# Wireless_Controller_V1_1.net
KiCad netlist of a schematic drawn in Altium Designer
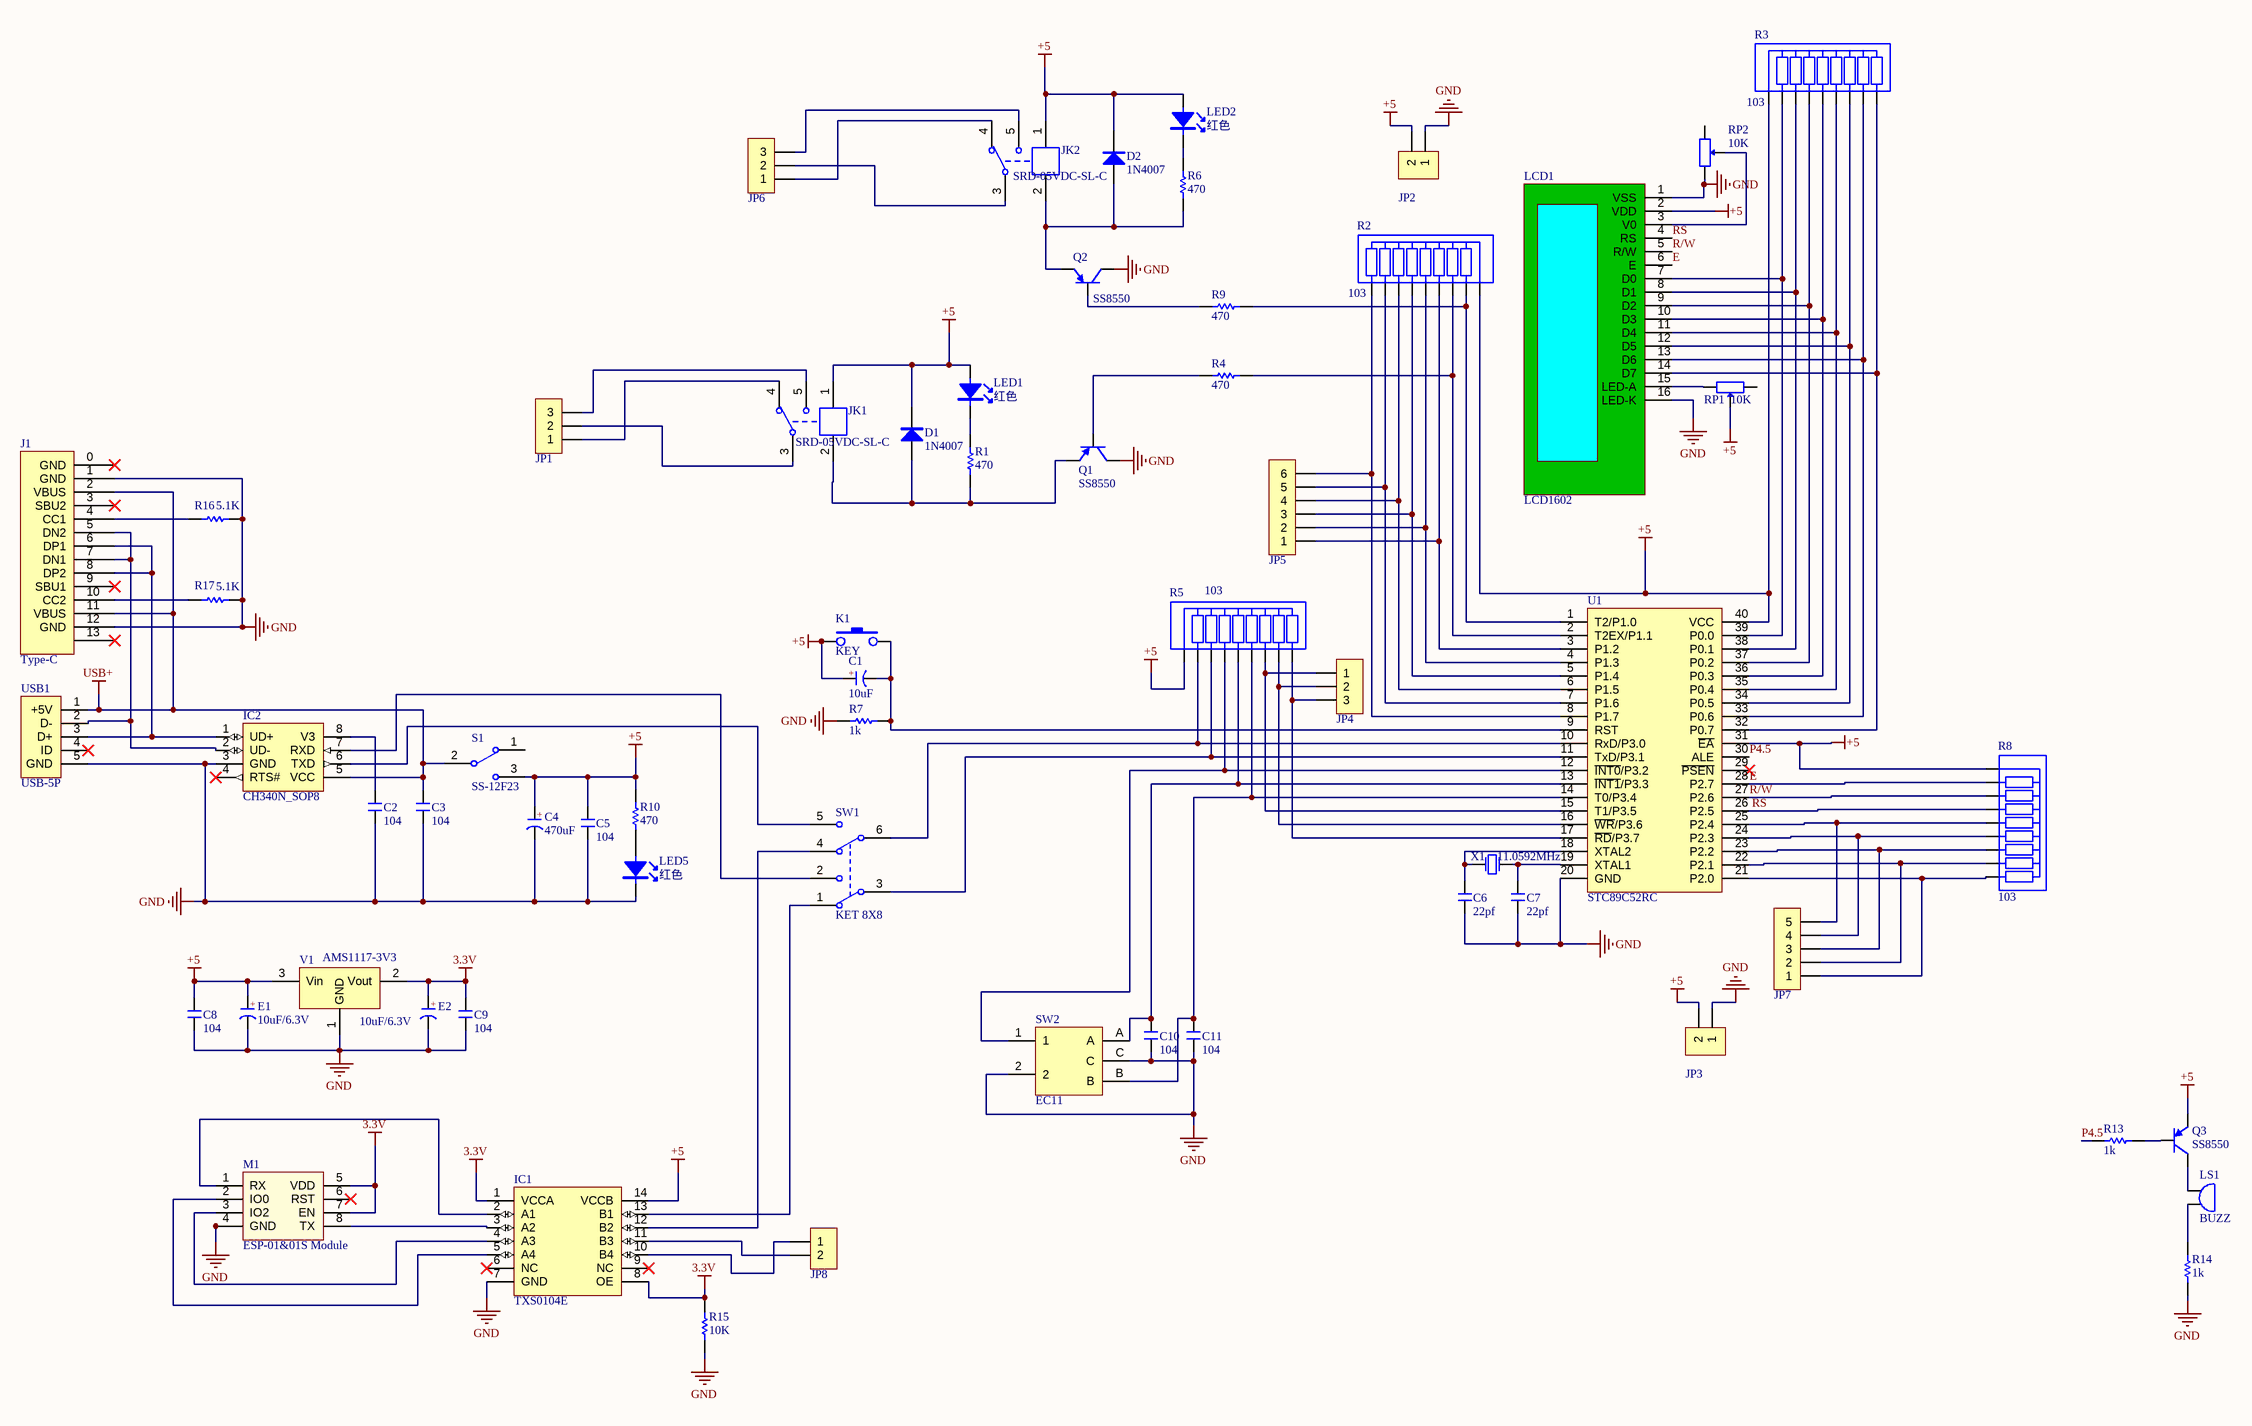
[diagram p0: Wireless_Controller_V1.1.SchDoc]

(export (version "E")
  (design (tool "Eeschema 10.0.6"))
  (components
    (comp (ref "C1")
      (value "10uF")
      (footprint "CAP 1.5*4*8")
      (description "直插电解电容")
      (libsource (lib "") (part "CE_1"))
    )
    (comp (ref "C2")
      (value "104")
      (footprint "CC 1.8*3.6")
      (description "瓷片电容")
      (libsource (lib "01 - 电容-电阻-电感") (part "CC"))
    )
    (comp (ref "C3")
      (value "104")
      (footprint "CC 1.8*3.6")
      (description "瓷片电容")
      (libsource (lib "01 - 电容-电阻-电感") (part "CC"))
    )
    (comp (ref "C4")
      (value "470uF")
      (footprint "CAP 2.5*6.3*11.2 - BK")
      (description "直插电解电容")
      (libsource (lib "01 - 电容-电阻-电感") (part "CE"))
    )
    (comp (ref "C5")
      (value "104")
      (footprint "CC 1.8*3.6")
      (description "瓷片电容")
      (libsource (lib "01 - 电容-电阻-电感") (part "CC"))
    )
    (comp (ref "C6")
      (value "22pf")
      (footprint "CC 1.8*3.6")
      (description "瓷片电容")
      (libsource (lib "01 - 电容-电阻-电感") (part "CC"))
    )
    (comp (ref "C7")
      (value "22pf")
      (footprint "CC 1.8*3.6")
      (description "瓷片电容")
      (libsource (lib "01 - 电容-电阻-电感") (part "CC"))
    )
    (comp (ref "C8")
      (value "104")
      (footprint "CC 1.8*3.6")
      (description "瓷片电容")
      (libsource (lib "01 - 电容-电阻-电感") (part "CC"))
    )
    (comp (ref "C9")
      (value "104")
      (footprint "CC 1.8*3.6")
      (description "瓷片电容")
      (libsource (lib "01 - 电容-电阻-电感") (part "CC"))
    )
    (comp (ref "C10")
      (value "104")
      (footprint "CC 1.8*3.6")
      (description "瓷片电容")
      (libsource (lib "01 - 电容-电阻-电感") (part "CC"))
    )
    (comp (ref "C11")
      (value "104")
      (footprint "CC 1.8*3.6")
      (description "瓷片电容")
      (libsource (lib "01 - 电容-电阻-电感") (part "CC"))
    )
    (comp (ref "D1")
      (value "1N4007")
      (footprint "DO-41")
      (description "整流二极管")
      (libsource (lib "02 - 二极管(LED)-三极管-整流桥") (part "1N4007"))
    )
    (comp (ref "D2")
      (value "1N4007")
      (footprint "DO-41")
      (description "整流二极管")
      (libsource (lib "02 - 二极管(LED)-三极管-整流桥") (part "1N4007"))
    )
    (comp (ref "E1")
      (value "10uF/6.3V")
      (footprint "CD S(2012)")
      (description "贴片钽电容")
      (libsource (lib "01 - 电容-电阻-电感") (part "CT"))
    )
    (comp (ref "E2")
      (value "10uF/6.3V")
      (footprint "CD S(2012)")
      (description "贴片钽电容")
      (libsource (lib "01 - 电容-电阻-电感") (part "CT"))
    )
    (comp (ref "IC1")
      (value "TXS0104E")
      (footprint "13 - TSSOP封装:TSSOP14_L")
      (description "TXS0104E_TSSOP(14pin)")
      (libsource (lib "TXS0104E_TSSOP(14pin)") (part "TXS0104E"))
    )
    (comp (ref "IC2")
      (value "CH340N_SOP8")
      (footprint "10 - SOP-SOIC封装:SOP8")
      (description "USB转串口芯片")
      (libsource (lib "CH340N_SOP-8") (part "CH340N_SOP8"))
    )
    (comp (ref "J1")
      (value "Type-C")
      (footprint "Type-C_16pin")
      (libsource (lib "Type-C_16PIN") (part "Type-C_16pin"))
    )
    (comp (ref "JK1")
      (value "SRD-05VDC-SL-C")
      (footprint "SRD-C_B")
      (description "继电器  5V一组转换")
      (libsource (lib "07 - 继电器-变压器-各种模块") (part "SRD-05VDC-SL-C"))
    )
    (comp (ref "JK2")
      (value "SRD-05VDC-SL-C")
      (footprint "SRD-C_B")
      (description "继电器  5V一组转换")
      (libsource (lib "07 - 继电器-变压器-各种模块") (part "SRD-05VDC-SL-C"))
    )
    (comp (ref "JP1")
      (value "HDR-1X3")
      (footprint "KF7620-3P")
      (description "3P接插件")
      (libsource (lib "24 - 接插件-脚距7.62mm (300mil) ") (part "Header 3"))
    )
    (comp (ref "JP2")
      (value "HDR-1X2")
      (footprint "KF7620-2P")
      (description "2P接插件")
      (libsource (lib "24 - 接插件-脚距7.62mm (300mil) ") (part "Header 2"))
    )
    (comp (ref "JP3")
      (value "HDR-1X2")
      (footprint "KF7620-2P")
      (description "2P接插件")
      (libsource (lib "24 - 接插件-脚距7.62mm (300mil) ") (part "Header 2"))
    )
    (comp (ref "JP4")
      (value "HDR-1X3")
      (footprint "KF301-5.0-3P")
      (description "3P接插件")
      (libsource (lib "22 - 接插件-脚距5.0mm") (part "Header 3"))
    )
    (comp (ref "JP5")
      (value "HDR-1X6")
      (footprint "KF301-5.0-6P")
      (description "6P接插件")
      (libsource (lib "22 - 接插件-脚距5.0mm") (part "Header 6"))
    )
    (comp (ref "JP6")
      (value "HDR-1X3")
      (footprint "KF7620-3P")
      (description "3P接插件")
      (libsource (lib "24 - 接插件-脚距7.62mm (300mil) ") (part "Header 3"))
    )
    (comp (ref "JP7")
      (value "HDR-1X5")
      (footprint "KF301-5.0-5P")
      (description "5P接插件")
      (libsource (lib "22 - 接插件-脚距5.0mm") (part "Header 5"))
    )
    (comp (ref "JP8")
      (value "HDR-1X2")
      (footprint "KF301-5.0-2P")
      (description "2P接插件")
      (libsource (lib "22 - 接插件-脚距5.0mm") (part "Header 2"))
    )
    (comp (ref "K1")
      (value "KEY")
      (footprint "TSW DIP-6*6*5")
      (description "四角直插开关")
      (libsource (lib "03 - 按键-开关-晶振-蜂鸣器") (part "KEY"))
    )
    (comp (ref "LCD1")
      (value "LCD1602")
      (footprint "LCD-1602")
      (libsource (lib "05 - 点阵-液晶-数码管-TFT") (part "LCD1602"))
    )
    (comp (ref "LED1")
      (value "红色")
      (footprint "LED 3MM-R")
      (description "插件LED")
      (libsource (lib "02 - 二极管(LED)-三极管-整流桥") (part "LED-3MM"))
    )
    (comp (ref "LED2")
      (value "红色")
      (footprint "LED 3MM-R")
      (description "插件LED")
      (libsource (lib "02 - 二极管(LED)-三极管-整流桥") (part "LED-3MM"))
    )
    (comp (ref "LED5")
      (value "红色")
      (footprint "LED 3MM-R")
      (description "插件LED")
      (libsource (lib "02 - 二极管(LED)-三极管-整流桥") (part "LED-3MM"))
    )
    (comp (ref "LS1")
      (value "BUZZ")
      (footprint "BEEP 6.5x12x8.5")
      (description "蜂鸣器")
      (libsource (lib "03 - 按键-开关-晶振-蜂鸣器") (part "BUZZ"))
    )
    (comp (ref "M1")
      (value "ESP-01&01S Module")
      (footprint "ESP-01&01S Module")
      (libsource (lib "ESP-01&01S Module") (part "ESP-01&01S Module"))
    )
    (comp (ref "Q1")
      (value "SS8550")
      (footprint "TO92A")
      (description "高频放大-PNP型")
      (libsource (lib "02 - 二极管(LED)-三极管-整流桥") (part "8550-DIP"))
    )
    (comp (ref "Q2")
      (value "SS8550")
      (footprint "TO92A")
      (description "高频放大-PNP型")
      (libsource (lib "02 - 二极管(LED)-三极管-整流桥") (part "8550-DIP"))
    )
    (comp (ref "Q3")
      (value "SS8550")
      (footprint "TO92A")
      (description "高频放大-PNP型")
      (libsource (lib "02 - 二极管(LED)-三极管-整流桥") (part "8550-DIP"))
    )
    (comp (ref "R1")
      (value "470")
      (footprint "RS 1/4W")
      (description "色环电阻")
      (libsource (lib "01 - 电容-电阻-电感") (part "Res"))
    )
    (comp (ref "R2")
      (value "103")
      (footprint "R SIP9-2.54")
      (description "9脚直插排阻")
      (libsource (lib "01 - 电容-电阻-电感") (part "R SIP9"))
    )
    (comp (ref "R3")
      (value "103")
      (footprint "R SIP9-2.54")
      (description "9脚直插排阻")
      (libsource (lib "01 - 电容-电阻-电感") (part "R SIP9"))
    )
    (comp (ref "R4")
      (value "470")
      (footprint "RS 1/4W")
      (description "色环电阻")
      (libsource (lib "01 - 电容-电阻-电感") (part "Res"))
    )
    (comp (ref "R5")
      (value "103")
      (footprint "R SIP9-2.54")
      (description "9脚直插排阻")
      (libsource (lib "01 - 电容-电阻-电感") (part "R SIP9"))
    )
    (comp (ref "R6")
      (value "470")
      (footprint "RS 1/4W")
      (description "色环电阻")
      (libsource (lib "01 - 电容-电阻-电感") (part "Res"))
    )
    (comp (ref "R7")
      (value "1k")
      (footprint "RS 1/4W")
      (description "色环电阻")
      (libsource (lib "01 - 电容-电阻-电感") (part "Res"))
    )
    (comp (ref "R8")
      (value "103")
      (footprint "R SIP9-2.54")
      (description "9脚直插排阻")
      (libsource (lib "01 - 电容-电阻-电感") (part "R SIP9"))
    )
    (comp (ref "R9")
      (value "470")
      (footprint "RS 1/4W")
      (description "色环电阻")
      (libsource (lib "01 - 电容-电阻-电感") (part "Res"))
    )
    (comp (ref "R10")
      (value "470")
      (footprint "RS 1/4W")
      (description "色环电阻")
      (libsource (lib "01 - 电容-电阻-电感") (part "Res"))
    )
    (comp (ref "R13")
      (value "1k")
      (footprint "RS 1/4W")
      (description "色环电阻")
      (libsource (lib "01 - 电容-电阻-电感") (part "Res"))
    )
    (comp (ref "R14")
      (value "1k")
      (footprint "RS 1/4W")
      (description "色环电阻")
      (libsource (lib "01 - 电容-电阻-电感") (part "Res"))
    )
    (comp (ref "R15")
      (value "10K")
      (footprint "RS 1/4W")
      (description "色环电阻")
      (libsource (lib "01 - 电容-电阻-电感") (part "Res"))
    )
    (comp (ref "R16")
      (value "5.1K")
      (footprint "RS 1/4W")
      (description "色环电阻")
      (libsource (lib "01 - 电容-电阻-电感") (part "Res"))
    )
    (comp (ref "R17")
      (value "5.1K")
      (footprint "RS 1/4W")
      (description "色环电阻")
      (libsource (lib "01 - 电容-电阻-电感") (part "Res"))
    )
    (comp (ref "RP1")
      (value "10K")
      (footprint "3296W")
      (description "单联电位器")
      (libsource (lib "01 - 电容-电阻-电感") (part "RP"))
    )
    (comp (ref "RP2")
      (value "10K")
      (footprint "3296W")
      (description "单联电位器")
      (libsource (lib "01 - 电容-电阻-电感") (part "RP"))
    )
    (comp (ref "S1")
      (value "SS-12F23")
      (footprint "SS-12D10")
      (description "1路波动开关")
      (libsource (lib "03 - 按键-开关-晶振-蜂鸣器") (part "SSW-1P"))
    )
    (comp (ref "SW1")
      (value "KET 8X8")
      (footprint "KFT DIP-8X8")
      (description "8*8自锁开关")
      (libsource (lib "03 - 按键-开关-晶振-蜂鸣器") (part "KET 8X8"))
    )
    (comp (ref "SW2")
      (value "EC11")
      (footprint "EC11")
      (description "数字开关编码器")
      (libsource (lib "03 - 按键-开关-晶振-蜂鸣器") (part "SW-EC11"))
    )
    (comp (ref "U1")
      (value "STC89C52RC")
      (footprint "DIP40-600")
      (description "STC单片机")
      (libsource (lib "26 - STC系列单片机") (part "STC89C52RC"))
    )
    (comp (ref "USB1")
      (value "USB-5P")
      (footprint "USB-MICRO_A")
      (description "微型USB母座")
      (libsource (lib "04 - 接口类-USB接口-网口") (part "USB-5P"))
    )
    (comp (ref "V1")
      (value "AMS1117-3V3")
      (footprint "SOT223_L")
      (description "三端稳压芯片")
      (libsource (lib "08 - 稳压芯片-电源管理芯片") (part "AMS1117"))
    )
    (comp (ref "X1")
      (value "11.0592MHz")
      (footprint "OSC HC-49S")
      (description "2脚无源脚晶振")
      (libsource (lib "03 - 按键-开关-晶振-蜂鸣器") (part "XTAL-2P"))
    )
  )
  (nets
    (net (code "1") (name "+5") (class "Default")
      (node (ref "C1") (pin "1") (pinfunction "A_1") (pintype "passive"))
      (node (ref "C4") (pin "1") (pinfunction "A_1") (pintype "passive"))
      (node (ref "C5") (pin "2") (pinfunction "2_2") (pintype "passive"))
      (node (ref "C8") (pin "2") (pinfunction "2_2") (pintype "passive"))
      (node (ref "D1") (pin "2") (pinfunction "K_2") (pintype "passive"))
      (node (ref "D2") (pin "2") (pinfunction "K_2") (pintype "passive"))
      (node (ref "E1") (pin "1") (pinfunction "A_1") (pintype "passive"))
      (node (ref "IC1") (pin "14") (pinfunction "VCCB_14") (pintype "power_in"))
      (node (ref "JK1") (pin "1") (pinfunction "1_1") (pintype "passive"))
      (node (ref "JK2") (pin "1") (pinfunction "1_1") (pintype "passive"))
      (node (ref "JP2") (pin "2") (pinfunction "2_2") (pintype "passive"))
      (node (ref "JP3") (pin "2") (pinfunction "2_2") (pintype "passive"))
      (node (ref "K1") (pin "1") (pinfunction "1_1") (pintype "passive"))
      (node (ref "LCD1") (pin "2") (pinfunction "VDD_2") (pintype "passive"))
      (node (ref "LED1") (pin "1") (pinfunction "A_1") (pintype "passive"))
      (node (ref "LED2") (pin "1") (pinfunction "A_1") (pintype "passive"))
      (node (ref "Q3") (pin "1") (pinfunction "E_1") (pintype "passive"))
      (node (ref "R10") (pin "2") (pinfunction "2_2") (pintype "passive"))
      (node (ref "R2") (pin "1") (pinfunction "1_1") (pintype "passive"))
      (node (ref "R3") (pin "1") (pinfunction "1_1") (pintype "passive"))
      (node (ref "R5") (pin "1") (pinfunction "1_1") (pintype "passive"))
      (node (ref "R8") (pin "1") (pinfunction "1_1") (pintype "passive"))
      (node (ref "RP1") (pin "2") (pinfunction "2_2") (pintype "passive"))
      (node (ref "S1") (pin "3") (pinfunction "3_3") (pintype "passive"))
      (node (ref "U1") (pin "31") (pinfunction "~{EA}_31") (pintype "passive"))
      (node (ref "U1") (pin "40") (pinfunction "VCC_40") (pintype "passive"))
      (node (ref "V1") (pin "3") (pinfunction "Vin_3") (pintype "passive"))
    )
    (net (code "2") (name "/E") (class "Default")
      (node (ref "LCD1") (pin "6") (pinfunction "E_6") (pintype "passive"))
      (node (ref "R8") (pin "2") (pinfunction "2_2") (pintype "passive"))
      (node (ref "U1") (pin "28") (pinfunction "P2.7_28") (pintype "passive"))
    )
    (net (code "3") (name "/P4.5") (class "Default")
      (node (ref "R13") (pin "2") (pinfunction "2_2") (pintype "passive"))
      (node (ref "U1") (pin "30") (pinfunction "ALE_30") (pintype "passive"))
    )
    (net (code "4") (name "/RS") (class "Default")
      (node (ref "LCD1") (pin "4") (pinfunction "RS_4") (pintype "passive"))
      (node (ref "R8") (pin "4") (pinfunction "4_4") (pintype "passive"))
      (node (ref "U1") (pin "26") (pinfunction "P2.5_26") (pintype "passive"))
    )
    (net (code "5") (name "/R{slash}W") (class "Default")
      (node (ref "LCD1") (pin "5") (pinfunction "R/W_5") (pintype "passive"))
      (node (ref "R8") (pin "3") (pinfunction "3_3") (pintype "passive"))
      (node (ref "U1") (pin "27") (pinfunction "P2.6_27") (pintype "passive"))
    )
    (net (code "6") (name "3.3V") (class "Default")
      (node (ref "C9") (pin "2") (pinfunction "2_2") (pintype "passive"))
      (node (ref "E2") (pin "1") (pinfunction "A_1") (pintype "passive"))
      (node (ref "IC1") (pin "1") (pinfunction "VCCA_1") (pintype "power_in"))
      (node (ref "IC1") (pin "8") (pinfunction "OE_8") (pintype "passive"))
      (node (ref "M1") (pin "5") (pinfunction "VDD_5") (pintype "passive"))
      (node (ref "M1") (pin "7") (pinfunction "EN_7") (pintype "passive"))
      (node (ref "R15") (pin "2") (pinfunction "2_2") (pintype "passive"))
      (node (ref "V1") (pin "2") (pinfunction "Vout_2") (pintype "passive"))
    )
    (net (code "7") (name "GND") (class "Default")
      (node (ref "C10") (pin "1") (pinfunction "1_1") (pintype "passive"))
      (node (ref "C11") (pin "1") (pinfunction "1_1") (pintype "passive"))
      (node (ref "C2") (pin "1") (pinfunction "1_1") (pintype "passive"))
      (node (ref "C3") (pin "1") (pinfunction "1_1") (pintype "passive"))
      (node (ref "C4") (pin "2") (pinfunction "K_2") (pintype "passive"))
      (node (ref "C5") (pin "1") (pinfunction "1_1") (pintype "passive"))
      (node (ref "C6") (pin "1") (pinfunction "1_1") (pintype "passive"))
      (node (ref "C7") (pin "1") (pinfunction "1_1") (pintype "passive"))
      (node (ref "C8") (pin "1") (pinfunction "1_1") (pintype "passive"))
      (node (ref "C9") (pin "1") (pinfunction "1_1") (pintype "passive"))
      (node (ref "E1") (pin "2") (pinfunction "K_2") (pintype "passive"))
      (node (ref "E2") (pin "2") (pinfunction "K_2") (pintype "passive"))
      (node (ref "IC1") (pin "7") (pinfunction "GND_7") (pintype "power_in"))
      (node (ref "IC2") (pin "3") (pinfunction "GND_3") (pintype "power_in"))
      (node (ref "J1") (pin "1") (pinfunction "GND_1") (pintype "passive"))
      (node (ref "J1") (pin "12") (pinfunction "GND_12") (pintype "passive"))
      (node (ref "JP2") (pin "1") (pinfunction "1_1") (pintype "passive"))
      (node (ref "JP3") (pin "1") (pinfunction "1_1") (pintype "passive"))
      (node (ref "LCD1") (pin "1") (pinfunction "VSS_1") (pintype "passive"))
      (node (ref "LCD1") (pin "16") (pinfunction "LED-K_16") (pintype "passive"))
      (node (ref "LED5") (pin "2") (pinfunction "K_2") (pintype "passive"))
      (node (ref "M1") (pin "4") (pinfunction "GND_4") (pintype "passive"))
      (node (ref "Q1") (pin "3") (pinfunction "C_3") (pintype "passive"))
      (node (ref "Q2") (pin "3") (pinfunction "C_3") (pintype "passive"))
      (node (ref "R14") (pin "2") (pinfunction "2_2") (pintype "passive"))
      (node (ref "R15") (pin "1") (pinfunction "1_1") (pintype "passive"))
      (node (ref "R16") (pin "2") (pinfunction "2_2") (pintype "passive"))
      (node (ref "R17") (pin "2") (pinfunction "2_2") (pintype "passive"))
      (node (ref "R7") (pin "2") (pinfunction "2_2") (pintype "passive"))
      (node (ref "RP2") (pin "3") (pinfunction "3_3") (pintype "passive"))
      (node (ref "SW2") (pin "2") (pinfunction "2_2") (pintype "passive"))
      (node (ref "SW2") (pin "C") (pinfunction "C_C") (pintype "passive"))
      (node (ref "U1") (pin "20") (pinfunction "GND_20") (pintype "passive"))
      (node (ref "USB1") (pin "5") (pinfunction "GND_5") (pintype "passive"))
      (node (ref "V1") (pin "1") (pinfunction "GND_1") (pintype "passive"))
    )
    (net (code "8") (name "Net-(C1-K)") (class "Default")
      (node (ref "C1") (pin "2") (pinfunction "K_2") (pintype "passive"))
      (node (ref "K1") (pin "2") (pinfunction "2_2") (pintype "passive"))
      (node (ref "R7") (pin "1") (pinfunction "1_1") (pintype "passive"))
      (node (ref "U1") (pin "9") (pinfunction "RST_9") (pintype "passive"))
    )
    (net (code "9") (name "Net-(D1-A)") (class "Default")
      (node (ref "D1") (pin "1") (pinfunction "A_1") (pintype "passive"))
      (node (ref "JK1") (pin "2") (pinfunction "2_2") (pintype "passive"))
      (node (ref "Q1") (pin "1") (pinfunction "E_1") (pintype "passive"))
      (node (ref "R1") (pin "2") (pinfunction "2_2") (pintype "passive"))
    )
    (net (code "10") (name "Net-(D2-A)") (class "Default")
      (node (ref "D2") (pin "1") (pinfunction "A_1") (pintype "passive"))
      (node (ref "JK2") (pin "2") (pinfunction "2_2") (pintype "passive"))
      (node (ref "Q2") (pin "1") (pinfunction "E_1") (pintype "passive"))
      (node (ref "R6") (pin "2") (pinfunction "2_2") (pintype "passive"))
    )
    (net (code "11") (name "Net-(IC1-A1)") (class "Default")
      (node (ref "IC1") (pin "2") (pinfunction "A1_2") (pintype "bidirectional"))
      (node (ref "M1") (pin "1") (pinfunction "RX_1") (pintype "passive"))
    )
    (net (code "12") (name "Net-(IC1-A2)") (class "Default")
      (node (ref "IC1") (pin "3") (pinfunction "A2_3") (pintype "bidirectional"))
      (node (ref "M1") (pin "8") (pinfunction "TX_8") (pintype "passive"))
    )
    (net (code "13") (name "Net-(IC1-A3)") (class "Default")
      (node (ref "IC1") (pin "4") (pinfunction "A3_4") (pintype "bidirectional"))
      (node (ref "M1") (pin "3") (pinfunction "IO2_3") (pintype "passive"))
    )
    (net (code "14") (name "Net-(IC1-A4)") (class "Default")
      (node (ref "IC1") (pin "5") (pinfunction "A4_5") (pintype "bidirectional"))
      (node (ref "M1") (pin "2") (pinfunction "IO0_2") (pintype "passive"))
    )
    (net (code "15") (name "Net-(IC1-B1)") (class "Default")
      (node (ref "IC1") (pin "13") (pinfunction "B1_13") (pintype "bidirectional"))
      (node (ref "SW1") (pin "1") (pinfunction "NC1_1") (pintype "passive"))
    )
    (net (code "16") (name "Net-(IC1-B2)") (class "Default")
      (node (ref "IC1") (pin "12") (pinfunction "B2_12") (pintype "bidirectional"))
      (node (ref "SW1") (pin "4") (pinfunction "NO2_4") (pintype "passive"))
    )
    (net (code "17") (name "Net-(IC1-B3)") (class "Default")
      (node (ref "IC1") (pin "11") (pinfunction "B3_11") (pintype "bidirectional"))
      (node (ref "JP8") (pin "2") (pinfunction "2_2") (pintype "passive"))
    )
    (net (code "18") (name "Net-(IC1-B4)") (class "Default")
      (node (ref "IC1") (pin "10") (pinfunction "B4_10") (pintype "bidirectional"))
      (node (ref "JP8") (pin "1") (pinfunction "1_1") (pintype "passive"))
    )
    (net (code "19") (name "Net-(IC2-RXD)") (class "Default")
      (node (ref "IC2") (pin "7") (pinfunction "RXD_7") (pintype "input"))
      (node (ref "SW1") (pin "2") (pinfunction "COM2_2") (pintype "passive"))
    )
    (net (code "20") (name "Net-(IC2-TXD)") (class "Default")
      (node (ref "IC2") (pin "6") (pinfunction "TXD_6") (pintype "output"))
      (node (ref "SW1") (pin "5") (pinfunction "COM2_5") (pintype "passive"))
    )
    (net (code "21") (name "Net-(IC2-UD+)") (class "Default")
      (node (ref "IC2") (pin "1") (pinfunction "UD+_1") (pintype "bidirectional"))
      (node (ref "J1") (pin "6") (pinfunction "DP1_6") (pintype "passive"))
      (node (ref "J1") (pin "8") (pinfunction "DP2_8") (pintype "passive"))
      (node (ref "USB1") (pin "3") (pinfunction "D+_3") (pintype "passive"))
    )
    (net (code "22") (name "Net-(IC2-UD-)") (class "Default")
      (node (ref "IC2") (pin "2") (pinfunction "UD-_2") (pintype "bidirectional"))
      (node (ref "J1") (pin "5") (pinfunction "DN2_5") (pintype "passive"))
      (node (ref "J1") (pin "7") (pinfunction "DN1_7") (pintype "passive"))
      (node (ref "USB1") (pin "2") (pinfunction "D-_2") (pintype "passive"))
    )
    (net (code "23") (name "Net-(IC2-V3)") (class "Default")
      (node (ref "C2") (pin "2") (pinfunction "2_2") (pintype "passive"))
      (node (ref "IC2") (pin "8") (pinfunction "V3_8") (pintype "passive"))
    )
    (net (code "24") (name "Net-(J1-CC1)") (class "Default")
      (node (ref "J1") (pin "4") (pinfunction "CC1_4") (pintype "passive"))
      (node (ref "R16") (pin "1") (pinfunction "1_1") (pintype "passive"))
    )
    (net (code "25") (name "Net-(J1-CC2)") (class "Default")
      (node (ref "J1") (pin "10") (pinfunction "CC2_10") (pintype "passive"))
      (node (ref "R17") (pin "1") (pinfunction "1_1") (pintype "passive"))
    )
    (net (code "26") (name "Net-(JK1-Pad3)") (class "Default")
      (node (ref "JK1") (pin "3") (pinfunction "3_3") (pintype "passive"))
      (node (ref "JP1") (pin "2") (pinfunction "2_2") (pintype "passive"))
    )
    (net (code "27") (name "Net-(JK1-Pad4)") (class "Default")
      (node (ref "JK1") (pin "4") (pinfunction "4_4") (pintype "passive"))
      (node (ref "JP1") (pin "1") (pinfunction "1_1") (pintype "passive"))
    )
    (net (code "28") (name "Net-(JK1-Pad5)") (class "Default")
      (node (ref "JK1") (pin "5") (pinfunction "5_5") (pintype "passive"))
      (node (ref "JP1") (pin "3") (pinfunction "3_3") (pintype "passive"))
    )
    (net (code "29") (name "Net-(JK2-Pad3)") (class "Default")
      (node (ref "JK2") (pin "3") (pinfunction "3_3") (pintype "passive"))
      (node (ref "JP6") (pin "2") (pinfunction "2_2") (pintype "passive"))
    )
    (net (code "30") (name "Net-(JK2-Pad4)") (class "Default")
      (node (ref "JK2") (pin "4") (pinfunction "4_4") (pintype "passive"))
      (node (ref "JP6") (pin "1") (pinfunction "1_1") (pintype "passive"))
    )
    (net (code "31") (name "Net-(JK2-Pad5)") (class "Default")
      (node (ref "JK2") (pin "5") (pinfunction "5_5") (pintype "passive"))
      (node (ref "JP6") (pin "3") (pinfunction "3_3") (pintype "passive"))
    )
    (net (code "32") (name "Net-(LCD1-D0)") (class "Default")
      (node (ref "LCD1") (pin "7") (pinfunction "D0_7") (pintype "passive"))
      (node (ref "R3") (pin "2") (pinfunction "2_2") (pintype "passive"))
      (node (ref "U1") (pin "39") (pinfunction "P0.0_39") (pintype "passive"))
    )
    (net (code "33") (name "Net-(LCD1-D1)") (class "Default")
      (node (ref "LCD1") (pin "8") (pinfunction "D1_8") (pintype "passive"))
      (node (ref "R3") (pin "3") (pinfunction "3_3") (pintype "passive"))
      (node (ref "U1") (pin "38") (pinfunction "P0.1_38") (pintype "passive"))
    )
    (net (code "34") (name "Net-(LCD1-D2)") (class "Default")
      (node (ref "LCD1") (pin "9") (pinfunction "D2_9") (pintype "passive"))
      (node (ref "R3") (pin "4") (pinfunction "4_4") (pintype "passive"))
      (node (ref "U1") (pin "37") (pinfunction "P0.2_37") (pintype "passive"))
    )
    (net (code "35") (name "Net-(LCD1-D3)") (class "Default")
      (node (ref "LCD1") (pin "10") (pinfunction "D3_10") (pintype "passive"))
      (node (ref "R3") (pin "5") (pinfunction "5_5") (pintype "passive"))
      (node (ref "U1") (pin "36") (pinfunction "P0.3_36") (pintype "passive"))
    )
    (net (code "36") (name "Net-(LCD1-D4)") (class "Default")
      (node (ref "LCD1") (pin "11") (pinfunction "D4_11") (pintype "passive"))
      (node (ref "R3") (pin "6") (pinfunction "6_6") (pintype "passive"))
      (node (ref "U1") (pin "35") (pinfunction "P0.4_35") (pintype "passive"))
    )
    (net (code "37") (name "Net-(LCD1-D5)") (class "Default")
      (node (ref "LCD1") (pin "12") (pinfunction "D5_12") (pintype "passive"))
      (node (ref "R3") (pin "7") (pinfunction "7_7") (pintype "passive"))
      (node (ref "U1") (pin "34") (pinfunction "P0.5_34") (pintype "passive"))
    )
    (net (code "38") (name "Net-(LCD1-D6)") (class "Default")
      (node (ref "LCD1") (pin "13") (pinfunction "D6_13") (pintype "passive"))
      (node (ref "R3") (pin "8") (pinfunction "8_8") (pintype "passive"))
      (node (ref "U1") (pin "33") (pinfunction "P0.6_33") (pintype "passive"))
    )
    (net (code "39") (name "Net-(LCD1-D7)") (class "Default")
      (node (ref "LCD1") (pin "14") (pinfunction "D7_14") (pintype "passive"))
      (node (ref "R3") (pin "9") (pinfunction "9_9") (pintype "passive"))
      (node (ref "U1") (pin "32") (pinfunction "P0.7_32") (pintype "passive"))
    )
    (net (code "40") (name "Net-(LCD1-LED-A)") (class "Default")
      (node (ref "LCD1") (pin "15") (pinfunction "LED-A_15") (pintype "passive"))
      (node (ref "RP1") (pin "3") (pinfunction "3_3") (pintype "passive"))
    )
    (net (code "41") (name "Net-(LCD1-V0)") (class "Default")
      (node (ref "LCD1") (pin "3") (pinfunction "V0_3") (pintype "passive"))
      (node (ref "RP2") (pin "2") (pinfunction "2_2") (pintype "passive"))
    )
    (net (code "42") (name "Net-(LED1-K)") (class "Default")
      (node (ref "LED1") (pin "2") (pinfunction "K_2") (pintype "passive"))
      (node (ref "R1") (pin "1") (pinfunction "1_1") (pintype "passive"))
    )
    (net (code "43") (name "Net-(LED2-K)") (class "Default")
      (node (ref "LED2") (pin "2") (pinfunction "K_2") (pintype "passive"))
      (node (ref "R6") (pin "1") (pinfunction "1_1") (pintype "passive"))
    )
    (net (code "44") (name "Net-(LED5-A)") (class "Default")
      (node (ref "LED5") (pin "1") (pinfunction "A_1") (pintype "passive"))
      (node (ref "R10") (pin "1") (pinfunction "1_1") (pintype "passive"))
    )
    (net (code "45") (name "Net-(LS1-Pad2)") (class "Default")
      (node (ref "LS1") (pin "2") (pinfunction "2_2") (pintype "passive"))
      (node (ref "R14") (pin "1") (pinfunction "1_1") (pintype "passive"))
    )
    (net (code "46") (name "Net-(Q1-B)") (class "Default")
      (node (ref "Q1") (pin "2") (pinfunction "B_2") (pintype "passive"))
      (node (ref "R4") (pin "1") (pinfunction "1_1") (pintype "passive"))
    )
    (net (code "47") (name "Net-(Q2-B)") (class "Default")
      (node (ref "Q2") (pin "2") (pinfunction "B_2") (pintype "passive"))
      (node (ref "R9") (pin "1") (pinfunction "1_1") (pintype "passive"))
    )
    (net (code "48") (name "Net-(Q3-B)") (class "Default")
      (node (ref "Q3") (pin "2") (pinfunction "B_2") (pintype "passive"))
      (node (ref "R13") (pin "1") (pinfunction "1_1") (pintype "passive"))
    )
    (net (code "49") (name "Net-(Q3-C)") (class "Default")
      (node (ref "LS1") (pin "1") (pinfunction "1_1") (pintype "passive"))
      (node (ref "Q3") (pin "3") (pinfunction "C_3") (pintype "passive"))
    )
    (net (code "50") (name "Net-(SW1-NC2)") (class "Default")
      (node (ref "R5") (pin "2") (pinfunction "2_2") (pintype "passive"))
      (node (ref "SW1") (pin "6") (pinfunction "NC2_6") (pintype "passive"))
      (node (ref "U1") (pin "10") (pinfunction "RxD/P3.0_10") (pintype "passive"))
    )
    (net (code "51") (name "Net-(SW1-NO1)") (class "Default")
      (node (ref "R5") (pin "3") (pinfunction "3_3") (pintype "passive"))
      (node (ref "SW1") (pin "3") (pinfunction "NO1_3") (pintype "passive"))
      (node (ref "U1") (pin "11") (pinfunction "TxD/P3.1_11") (pintype "passive"))
    )
    (net (code "52") (name "Net-(U1-P1.2)") (class "Default")
      (node (ref "JP5") (pin "1") (pinfunction "1_1") (pintype "passive"))
      (node (ref "R2") (pin "4") (pinfunction "4_4") (pintype "passive"))
      (node (ref "U1") (pin "3") (pinfunction "P1.2_3") (pintype "passive"))
    )
    (net (code "53") (name "Net-(U1-P1.3)") (class "Default")
      (node (ref "JP5") (pin "2") (pinfunction "2_2") (pintype "passive"))
      (node (ref "R2") (pin "5") (pinfunction "5_5") (pintype "passive"))
      (node (ref "U1") (pin "4") (pinfunction "P1.3_4") (pintype "passive"))
    )
    (net (code "54") (name "Net-(U1-P1.4)") (class "Default")
      (node (ref "JP5") (pin "3") (pinfunction "3_3") (pintype "passive"))
      (node (ref "R2") (pin "6") (pinfunction "6_6") (pintype "passive"))
      (node (ref "U1") (pin "5") (pinfunction "P1.4_5") (pintype "passive"))
    )
    (net (code "55") (name "Net-(U1-P1.5)") (class "Default")
      (node (ref "JP5") (pin "4") (pinfunction "4_4") (pintype "passive"))
      (node (ref "R2") (pin "7") (pinfunction "7_7") (pintype "passive"))
      (node (ref "U1") (pin "6") (pinfunction "P1.5_6") (pintype "passive"))
    )
    (net (code "56") (name "Net-(U1-P1.6)") (class "Default")
      (node (ref "JP5") (pin "5") (pinfunction "5_5") (pintype "passive"))
      (node (ref "R2") (pin "8") (pinfunction "8_8") (pintype "passive"))
      (node (ref "U1") (pin "7") (pinfunction "P1.6_7") (pintype "passive"))
    )
    (net (code "57") (name "Net-(U1-P1.7)") (class "Default")
      (node (ref "JP5") (pin "6") (pinfunction "6_6") (pintype "passive"))
      (node (ref "R2") (pin "9") (pinfunction "9_9") (pintype "passive"))
      (node (ref "U1") (pin "8") (pinfunction "P1.7_8") (pintype "passive"))
    )
    (net (code "58") (name "Net-(U1-P2.0)") (class "Default")
      (node (ref "JP7") (pin "1") (pinfunction "1_1") (pintype "passive"))
      (node (ref "R8") (pin "9") (pinfunction "9_9") (pintype "passive"))
      (node (ref "U1") (pin "21") (pinfunction "P2.0_21") (pintype "passive"))
    )
    (net (code "59") (name "Net-(U1-P2.1)") (class "Default")
      (node (ref "JP7") (pin "2") (pinfunction "2_2") (pintype "passive"))
      (node (ref "R8") (pin "8") (pinfunction "8_8") (pintype "passive"))
      (node (ref "U1") (pin "22") (pinfunction "P2.1_22") (pintype "passive"))
    )
    (net (code "60") (name "Net-(U1-P2.2)") (class "Default")
      (node (ref "JP7") (pin "3") (pinfunction "3_3") (pintype "passive"))
      (node (ref "R8") (pin "7") (pinfunction "7_7") (pintype "passive"))
      (node (ref "U1") (pin "23") (pinfunction "P2.2_23") (pintype "passive"))
    )
    (net (code "61") (name "Net-(U1-P2.3)") (class "Default")
      (node (ref "JP7") (pin "4") (pinfunction "4_4") (pintype "passive"))
      (node (ref "R8") (pin "6") (pinfunction "6_6") (pintype "passive"))
      (node (ref "U1") (pin "24") (pinfunction "P2.3_24") (pintype "passive"))
    )
    (net (code "62") (name "Net-(U1-P2.4)") (class "Default")
      (node (ref "JP7") (pin "5") (pinfunction "5_5") (pintype "passive"))
      (node (ref "R8") (pin "5") (pinfunction "5_5") (pintype "passive"))
      (node (ref "U1") (pin "25") (pinfunction "P2.4_25") (pintype "passive"))
    )
    (net (code "63") (name "Net-(U1-T0{slash}P3.4)") (class "Default")
      (node (ref "C11") (pin "2") (pinfunction "2_2") (pintype "passive"))
      (node (ref "R5") (pin "6") (pinfunction "6_6") (pintype "passive"))
      (node (ref "SW2") (pin "B") (pinfunction "B_B") (pintype "passive"))
      (node (ref "U1") (pin "14") (pinfunction "T0/P3.4_14") (pintype "passive"))
    )
    (net (code "64") (name "Net-(U1-T1{slash}P3.5)") (class "Default")
      (node (ref "JP4") (pin "1") (pinfunction "1_1") (pintype "passive"))
      (node (ref "R5") (pin "7") (pinfunction "7_7") (pintype "passive"))
      (node (ref "U1") (pin "15") (pinfunction "T1/P3.5_15") (pintype "passive"))
    )
    (net (code "65") (name "Net-(U1-T2EX{slash}P1.1)") (class "Default")
      (node (ref "R2") (pin "3") (pinfunction "3_3") (pintype "passive"))
      (node (ref "R4") (pin "2") (pinfunction "2_2") (pintype "passive"))
      (node (ref "U1") (pin "2") (pinfunction "T2EX/P1.1_2") (pintype "passive"))
    )
    (net (code "66") (name "Net-(U1-T2{slash}P1.0)") (class "Default")
      (node (ref "R2") (pin "2") (pinfunction "2_2") (pintype "passive"))
      (node (ref "R9") (pin "2") (pinfunction "2_2") (pintype "passive"))
      (node (ref "U1") (pin "1") (pinfunction "T2/P1.0_1") (pintype "passive"))
    )
    (net (code "67") (name "Net-(U1-XTAL1)") (class "Default")
      (node (ref "C7") (pin "2") (pinfunction "2_2") (pintype "passive"))
      (node (ref "U1") (pin "19") (pinfunction "XTAL1_19") (pintype "passive"))
      (node (ref "X1") (pin "2") (pinfunction "2_2") (pintype "passive"))
    )
    (net (code "68") (name "Net-(U1-XTAL2)") (class "Default")
      (node (ref "C6") (pin "2") (pinfunction "2_2") (pintype "passive"))
      (node (ref "U1") (pin "18") (pinfunction "XTAL2_18") (pintype "passive"))
      (node (ref "X1") (pin "1") (pinfunction "1_1") (pintype "passive"))
    )
    (net (code "69") (name "Net-(U1-~{INT0}{slash}P3.2)") (class "Default")
      (node (ref "R5") (pin "4") (pinfunction "4_4") (pintype "passive"))
      (node (ref "SW2") (pin "1") (pinfunction "1_1") (pintype "passive"))
      (node (ref "U1") (pin "12") (pinfunction "~{INT0}/P3.2_12") (pintype "passive"))
    )
    (net (code "70") (name "Net-(U1-~{INT1}{slash}P3.3)") (class "Default")
      (node (ref "C10") (pin "2") (pinfunction "2_2") (pintype "passive"))
      (node (ref "R5") (pin "5") (pinfunction "5_5") (pintype "passive"))
      (node (ref "SW2") (pin "A") (pinfunction "A_A") (pintype "passive"))
      (node (ref "U1") (pin "13") (pinfunction "~{INT1}/P3.3_13") (pintype "passive"))
    )
    (net (code "71") (name "Net-(U1-~{RD}{slash}P3.7)") (class "Default")
      (node (ref "JP4") (pin "3") (pinfunction "3_3") (pintype "passive"))
      (node (ref "R5") (pin "9") (pinfunction "9_9") (pintype "passive"))
      (node (ref "U1") (pin "17") (pinfunction "~{RD}/P3.7_17") (pintype "passive"))
    )
    (net (code "72") (name "Net-(U1-~{WR}{slash}P3.6)") (class "Default")
      (node (ref "JP4") (pin "2") (pinfunction "2_2") (pintype "passive"))
      (node (ref "R5") (pin "8") (pinfunction "8_8") (pintype "passive"))
      (node (ref "U1") (pin "16") (pinfunction "~{WR}/P3.6_16") (pintype "passive"))
    )
    (net (code "73") (name "USB+") (class "Default")
      (node (ref "C3") (pin "2") (pinfunction "2_2") (pintype "passive"))
      (node (ref "IC2") (pin "5") (pinfunction "VCC_5") (pintype "power_in"))
      (node (ref "J1") (pin "11") (pinfunction "VBUS_11") (pintype "passive"))
      (node (ref "J1") (pin "2") (pinfunction "VBUS_2") (pintype "passive"))
      (node (ref "S1") (pin "2") (pinfunction "2_2") (pintype "passive"))
      (node (ref "USB1") (pin "1") (pinfunction "+5V_1") (pintype "passive"))
    )
    (net (code "74") (name "unconnected-(IC1-NC-Pad6)") (class "Default")
      (node (ref "IC1") (pin "6") (pinfunction "NC_6") (pintype "passive+no_connect"))
    )
    (net (code "75") (name "unconnected-(IC1-NC-Pad9)") (class "Default")
      (node (ref "IC1") (pin "9") (pinfunction "NC_9") (pintype "passive+no_connect"))
    )
    (net (code "76") (name "unconnected-(IC2-RTS#-Pad4)") (class "Default")
      (node (ref "IC2") (pin "4") (pinfunction "RTS#_4") (pintype "output+no_connect"))
    )
    (net (code "77") (name "unconnected-(J1-GND-Pad0)") (class "Default")
      (node (ref "J1") (pin "0") (pinfunction "GND_0") (pintype "passive+no_connect"))
    )
    (net (code "78") (name "unconnected-(J1-Pad13)") (class "Default")
      (node (ref "J1") (pin "13") (pintype "passive+no_connect"))
    )
    (net (code "79") (name "unconnected-(J1-SBU1-Pad9)") (class "Default")
      (node (ref "J1") (pin "9") (pinfunction "SBU1_9") (pintype "passive+no_connect"))
    )
    (net (code "80") (name "unconnected-(J1-SBU2-Pad3)") (class "Default")
      (node (ref "J1") (pin "3") (pinfunction "SBU2_3") (pintype "passive+no_connect"))
    )
    (net (code "81") (name "unconnected-(M1-RST-Pad6)") (class "Default")
      (node (ref "M1") (pin "6") (pinfunction "RST_6") (pintype "passive+no_connect"))
    )
    (net (code "82") (name "unconnected-(RP1-Pad1)") (class "Default")
      (node (ref "RP1") (pin "1") (pinfunction "1_1") (pintype "passive"))
    )
    (net (code "83") (name "unconnected-(RP2-Pad1)") (class "Default")
      (node (ref "RP2") (pin "1") (pinfunction "1_1") (pintype "passive"))
    )
    (net (code "84") (name "unconnected-(S1-Pad1)") (class "Default")
      (node (ref "S1") (pin "1") (pinfunction "1_1") (pintype "passive"))
    )
    (net (code "85") (name "unconnected-(U1-~{PSEN}-Pad29)") (class "Default")
      (node (ref "U1") (pin "29") (pinfunction "~{PSEN}_29") (pintype "passive+no_connect"))
    )
    (net (code "86") (name "unconnected-(USB1-ID-Pad4)") (class "Default")
      (node (ref "USB1") (pin "4") (pinfunction "ID_4") (pintype "passive+no_connect"))
    )
  )
)
